# bk-circ1-S.net
KiCad netlist of a schematic drawn in EAGLE
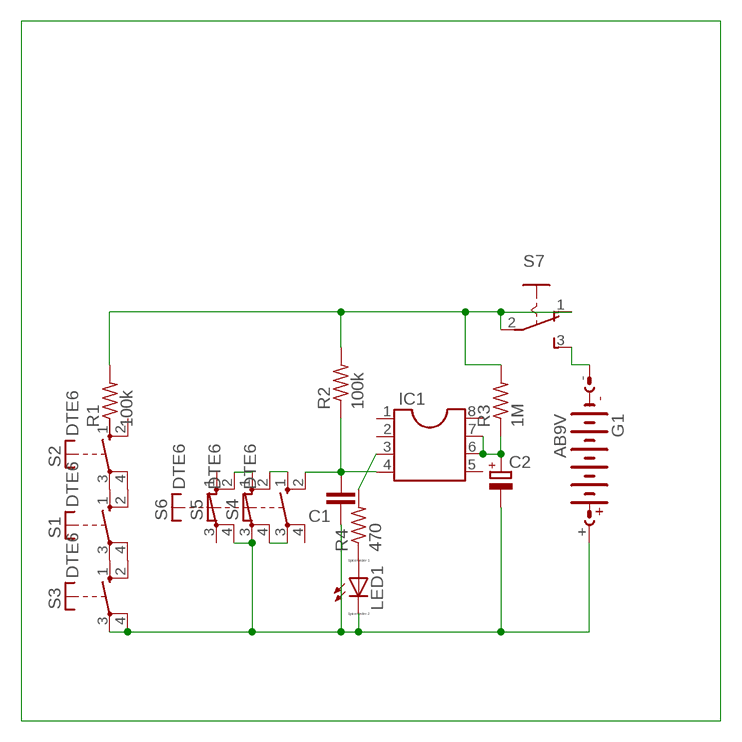
[diagram p0: schematic, sheet 1]

(export (version "E")
  (design (tool "Eeschema 10.0.6"))
  (components
    (comp (ref "C1")
      (value "C-EU025-030X050")
      (footprint "eagle-import:C025-030X050")
      (libsource (lib "eagle-import") (part "C-EU025-030X050"))
    )
    (comp (ref "C2")
      (value "CPOL-EUB45181B")
      (footprint "eagle-import:B45181B")
      (libsource (lib "eagle-import") (part "CPOL-EUB45181B"))
    )
    (comp (ref "G1")
      (value "AB9V")
      (footprint "eagle-import:AB9V")
      (libsource (lib "eagle-import") (part "AB9V"))
    )
    (comp (ref "IC1")
      (value "DIL8")
      (footprint "eagle-import:DIL08")
      (libsource (lib "eagle-import") (part "DIL8"))
    )
    (comp (ref "LED1")
      (value "LED_ELD260")
      (footprint "eagle-import:LED_LD260")
      (libsource (lib "eagle-import") (part "LED_ELD260"))
    )
    (comp (ref "R1")
      (value "100k")
      (footprint "eagle-import:0207_7")
      (libsource (lib "eagle-import") (part "R-US_0207/7"))
    )
    (comp (ref "R2")
      (value "100k")
      (footprint "eagle-import:0207_7")
      (libsource (lib "eagle-import") (part "R-US_0207/7"))
    )
    (comp (ref "R3")
      (value "1M")
      (footprint "eagle-import:0207_7")
      (libsource (lib "eagle-import") (part "R-US_0207/7"))
    )
    (comp (ref "R4")
      (value "470")
      (footprint "eagle-import:0207_7")
      (libsource (lib "eagle-import") (part "R-US_0207/7"))
    )
    (comp (ref "S1")
      (value "DTE6")
      (footprint "eagle-import:DTE6")
      (libsource (lib "eagle-import") (part "DTE6"))
    )
    (comp (ref "S2")
      (value "DTE6")
      (footprint "eagle-import:DTE6")
      (libsource (lib "eagle-import") (part "DTE6"))
    )
    (comp (ref "S3")
      (value "DTE6")
      (footprint "eagle-import:DTE6")
      (libsource (lib "eagle-import") (part "DTE6"))
    )
    (comp (ref "S4")
      (value "DTE6")
      (footprint "eagle-import:DTE6")
      (libsource (lib "eagle-import") (part "DTE6"))
    )
    (comp (ref "S5")
      (value "DTE6")
      (footprint "eagle-import:DTE6")
      (libsource (lib "eagle-import") (part "DTE6"))
    )
    (comp (ref "S6")
      (value "DTE6")
      (footprint "eagle-import:DTE6")
      (libsource (lib "eagle-import") (part "DTE6"))
    )
    (comp (ref "S7")
      (value "255SB")
      (footprint "eagle-import:255SB")
      (libsource (lib "eagle-import") (part "255SB"))
    )
  )
  (nets
    (net (code "1") (name "Net-(C1-Pad2)") (class "Default")
      (node (ref "C1") (pin "2") (pinfunction "2_2") (pintype "passive"))
      (node (ref "IC1") (pin "4") (pinfunction "4_4") (pintype "passive"))
      (node (ref "R2") (pin "1") (pinfunction "1_1") (pintype "passive"))
      (node (ref "S4") (pin "2") (pinfunction "S_2") (pintype "passive"))
    )
    (net (code "2") (name "Net-(C2-Pad+)") (class "Default")
      (node (ref "C2") (pin "+") (pinfunction "+_+") (pintype "passive"))
      (node (ref "IC1") (pin "6") (pinfunction "6_6") (pintype "passive"))
      (node (ref "IC1") (pin "7") (pinfunction "7_7") (pintype "passive"))
      (node (ref "R3") (pin "1") (pinfunction "1_1") (pintype "passive"))
    )
    (net (code "3") (name "Net-(IC1-Pad3)") (class "Default")
      (node (ref "IC1") (pin "3") (pinfunction "3_3") (pintype "passive"))
      (node (ref "R4") (pin "2") (pinfunction "2_2") (pintype "passive"))
    )
    (net (code "4") (name "Net-(LED1-C)") (class "Default")
      (node (ref "C1") (pin "1") (pinfunction "1_1") (pintype "passive"))
      (node (ref "C2") (pin "-") (pinfunction "-_-") (pintype "passive"))
      (node (ref "G1") (pin "+") (pinfunction "+_+") (pintype "passive"))
      (node (ref "LED1") (pin "K") (pinfunction "C_K") (pintype "passive"))
      (node (ref "S3") (pin "3") (pinfunction "P_3") (pintype "passive"))
      (node (ref "S3") (pin "4") (pinfunction "P_4") (pintype "passive"))
      (node (ref "S5") (pin "3") (pinfunction "P_3") (pintype "passive"))
      (node (ref "S6") (pin "4") (pinfunction "P_4") (pintype "passive"))
    )
    (net (code "5") (name "Net-(LED1-PadA)") (class "Default")
      (node (ref "LED1") (pin "A") (pinfunction "A_A") (pintype "passive"))
      (node (ref "R4") (pin "1") (pinfunction "1_1") (pintype "passive"))
    )
    (net (code "6") (name "Net-(S1-P-Pad3)") (class "Default")
      (node (ref "S1") (pin "3") (pinfunction "P_3") (pintype "passive"))
      (node (ref "S3") (pin "1") (pinfunction "S_1") (pintype "passive"))
    )
    (net (code "7") (name "Net-(S1-P-Pad4)") (class "Default")
      (node (ref "S1") (pin "4") (pinfunction "P_4") (pintype "passive"))
      (node (ref "S3") (pin "2") (pinfunction "S_2") (pintype "passive"))
    )
    (net (code "8") (name "Net-(S1-S-Pad1)") (class "Default")
      (node (ref "S1") (pin "1") (pinfunction "S_1") (pintype "passive"))
      (node (ref "S2") (pin "3") (pinfunction "P_3") (pintype "passive"))
    )
    (net (code "9") (name "Net-(S1-S-Pad2)") (class "Default")
      (node (ref "S1") (pin "2") (pinfunction "S_2") (pintype "passive"))
      (node (ref "S2") (pin "4") (pinfunction "P_4") (pintype "passive"))
    )
    (net (code "10") (name "Net-(S4-P-Pad3)") (class "Default")
      (node (ref "S4") (pin "3") (pinfunction "P_3") (pintype "passive"))
      (node (ref "S5") (pin "4") (pinfunction "P_4") (pintype "passive"))
    )
    (net (code "11") (name "Net-(S4-S-Pad1)") (class "Default")
      (node (ref "S4") (pin "1") (pinfunction "S_1") (pintype "passive"))
      (node (ref "S5") (pin "2") (pinfunction "S_2") (pintype "passive"))
    )
    (net (code "12") (name "Net-(S5-S-Pad1)") (class "Default")
      (node (ref "S5") (pin "1") (pinfunction "S_1") (pintype "passive"))
      (node (ref "S6") (pin "2") (pinfunction "S_2") (pintype "passive"))
    )
    (net (code "13") (name "Net-(S7-O)") (class "Default")
      (node (ref "R1") (pin "2") (pinfunction "2_2") (pintype "passive"))
      (node (ref "R2") (pin "2") (pinfunction "2_2") (pintype "passive"))
      (node (ref "R3") (pin "2") (pinfunction "2_2") (pintype "passive"))
      (node (ref "S7") (pin "1") (pinfunction "O_1") (pintype "passive"))
      (node (ref "S7") (pin "2") (pinfunction "P_2") (pintype "passive"))
    )
    (net (code "14") (name "Net-(S7-S)") (class "Default")
      (node (ref "G1") (pin "-") (pinfunction "-_-") (pintype "passive"))
      (node (ref "S7") (pin "3") (pinfunction "S_3") (pintype "passive"))
    )
    (net (code "15") (name "unconnected-(IC1-Pad1)") (class "Default")
      (node (ref "IC1") (pin "1") (pinfunction "1_1") (pintype "passive"))
    )
    (net (code "16") (name "unconnected-(IC1-Pad2)") (class "Default")
      (node (ref "IC1") (pin "2") (pinfunction "2_2") (pintype "passive"))
    )
    (net (code "17") (name "unconnected-(IC1-Pad5)") (class "Default")
      (node (ref "IC1") (pin "5") (pinfunction "5_5") (pintype "passive"))
    )
    (net (code "18") (name "unconnected-(IC1-Pad8)") (class "Default")
      (node (ref "IC1") (pin "8") (pinfunction "8_8") (pintype "passive"))
    )
    (net (code "19") (name "unconnected-(R1-Pad1)") (class "Default")
      (node (ref "R1") (pin "1") (pinfunction "1_1") (pintype "passive"))
    )
    (net (code "20") (name "unconnected-(S2-S-Pad1)") (class "Default")
      (node (ref "S2") (pin "1") (pinfunction "S_1") (pintype "passive"))
    )
    (net (code "21") (name "unconnected-(S2-S-Pad2)") (class "Default")
      (node (ref "S2") (pin "2") (pinfunction "S_2") (pintype "passive"))
    )
    (net (code "22") (name "unconnected-(S4-P-Pad4)") (class "Default")
      (node (ref "S4") (pin "4") (pinfunction "P_4") (pintype "passive"))
    )
    (net (code "23") (name "unconnected-(S6-P-Pad3)") (class "Default")
      (node (ref "S6") (pin "3") (pinfunction "P_3") (pintype "passive"))
    )
    (net (code "24") (name "unconnected-(S6-S-Pad1)") (class "Default")
      (node (ref "S6") (pin "1") (pinfunction "S_1") (pintype "passive"))
    )
  )
)
